# v1.net
KiCad netlist of a schematic drawn in EAGLE
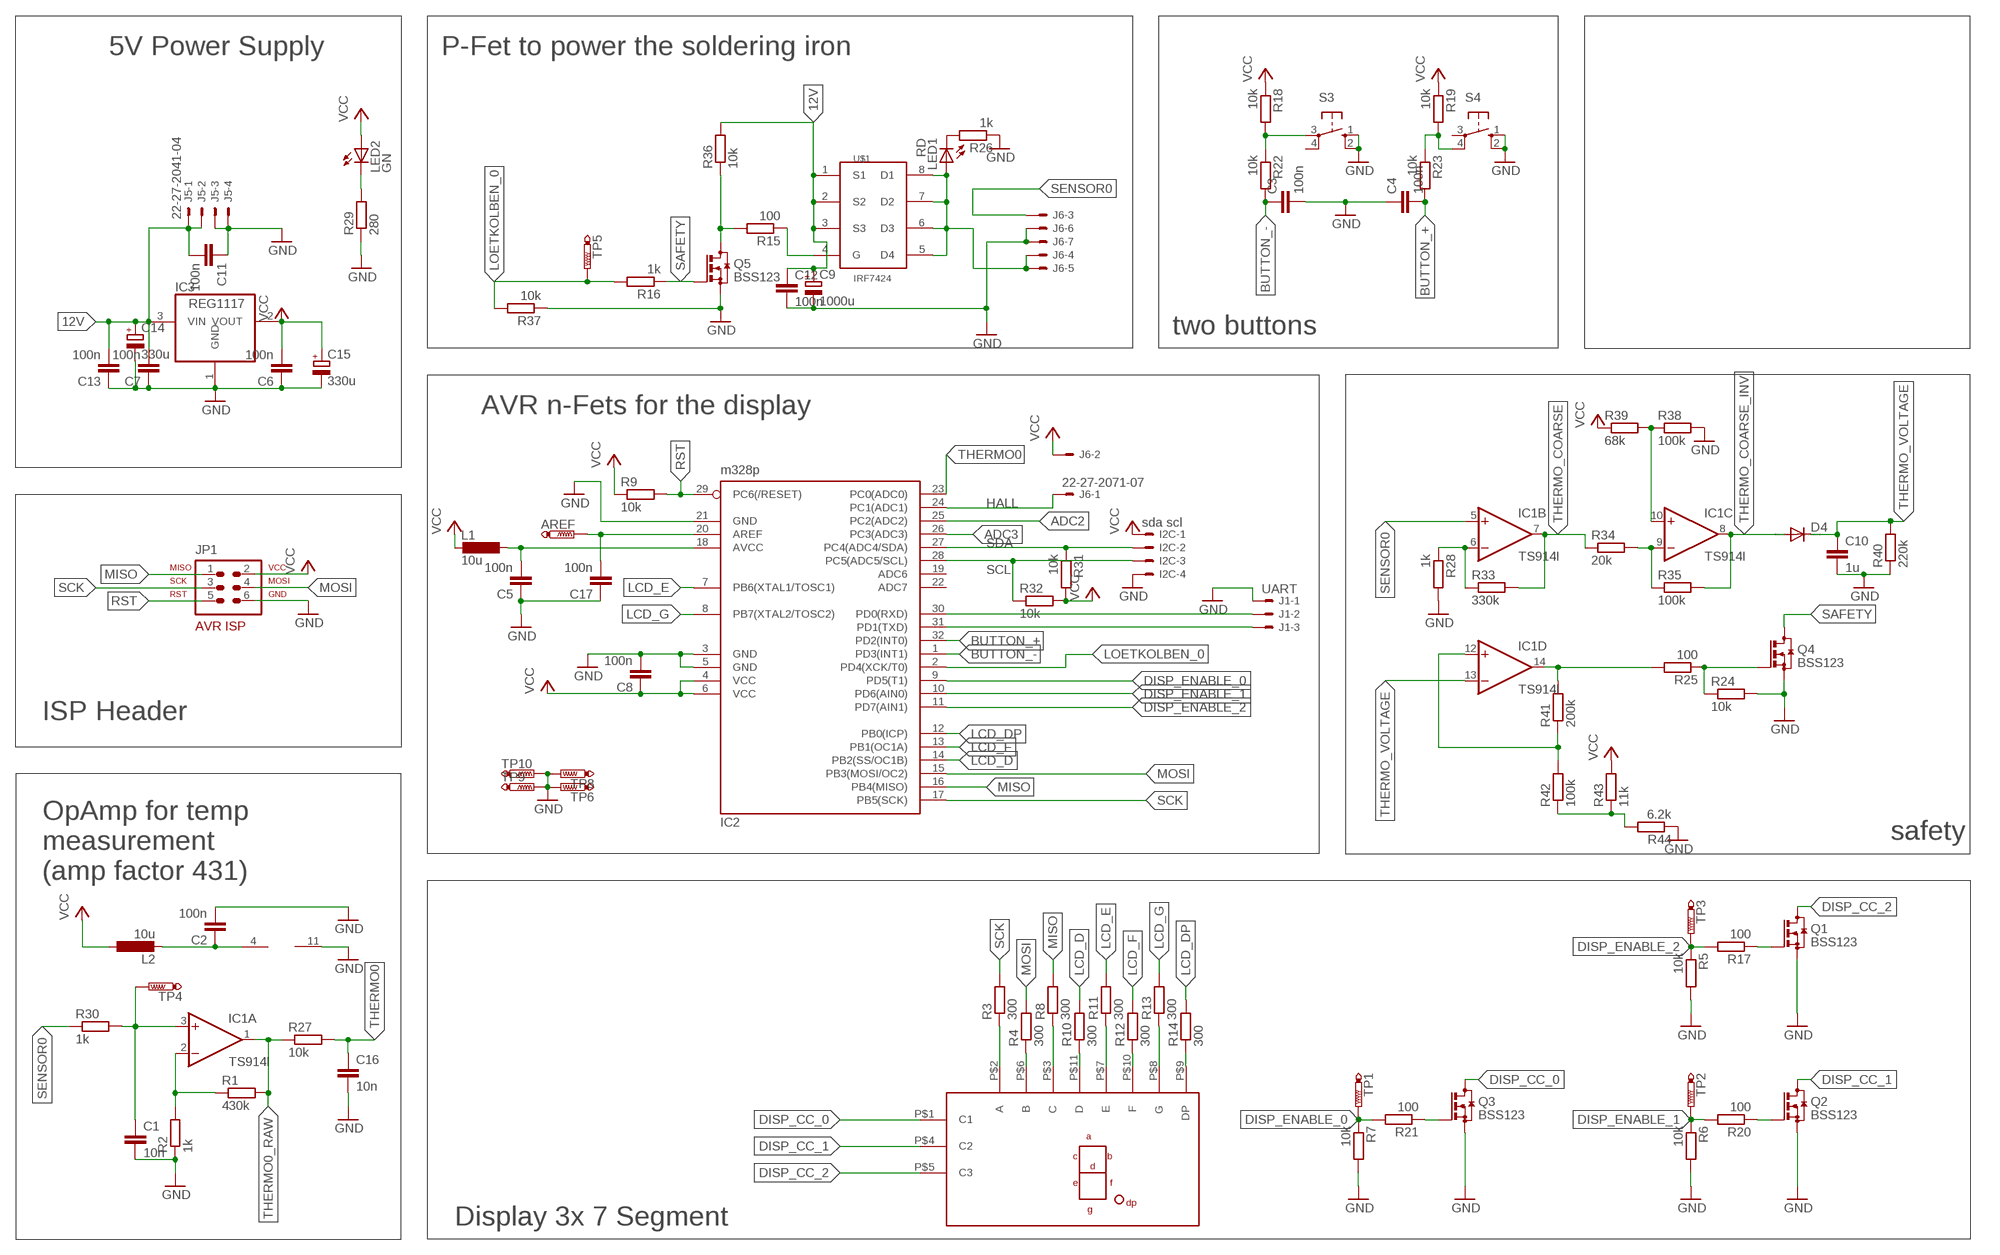
[diagram p0: schematic, sheet 1]

(export (version "E")
  (design (tool "Eeschema 10.0.6"))
  (components
    (comp (ref "AREF")
      (value "PTR1B1,27")
      (footprint "eagle-import:B1,27")
      (libsource (lib "eagle-import") (part "PTR1B1,27"))
    )
    (comp (ref "C1")
      (value "10n")
      (footprint "eagle-import:C0603")
      (libsource (lib "eagle-import") (part "C-EUC0603"))
    )
    (comp (ref "C2")
      (value "100n")
      (footprint "eagle-import:C0603")
      (libsource (lib "eagle-import") (part "C-EUC0603"))
    )
    (comp (ref "C3")
      (value "100n")
      (footprint "eagle-import:C0603")
      (libsource (lib "eagle-import") (part "C-EUC0603"))
    )
    (comp (ref "C4")
      (value "100n")
      (footprint "eagle-import:C0603")
      (libsource (lib "eagle-import") (part "C-EUC0603"))
    )
    (comp (ref "C5")
      (value "100n")
      (footprint "eagle-import:C0603")
      (libsource (lib "eagle-import") (part "C-EUC0603"))
    )
    (comp (ref "C6")
      (value "100n")
      (footprint "eagle-import:C0603")
      (libsource (lib "eagle-import") (part "C-EUC0603"))
    )
    (comp (ref "C7")
      (value "100n")
      (footprint "eagle-import:C0603")
      (libsource (lib "eagle-import") (part "C-EUC0603"))
    )
    (comp (ref "C8")
      (value "100n")
      (footprint "eagle-import:C0603")
      (libsource (lib "eagle-import") (part "C-EUC0603"))
    )
    (comp (ref "C9")
      (value "1000u")
      (footprint "eagle-import:E5-13")
      (libsource (lib "eagle-import") (part "CPOL-EUE5-13"))
    )
    (comp (ref "C10")
      (value "1u")
      (footprint "eagle-import:C0805")
      (libsource (lib "eagle-import") (part "C-EUC0805"))
    )
    (comp (ref "C11")
      (value "100n")
      (footprint "eagle-import:C0603")
      (libsource (lib "eagle-import") (part "C-EUC0603"))
    )
    (comp (ref "C12")
      (value "100n")
      (footprint "eagle-import:C0603")
      (libsource (lib "eagle-import") (part "C-EUC0603"))
    )
    (comp (ref "C13")
      (value "100n")
      (footprint "eagle-import:C0603")
      (libsource (lib "eagle-import") (part "C-EUC0603"))
    )
    (comp (ref "C14")
      (value "330u")
      (footprint "eagle-import:E3,5-8")
      (libsource (lib "eagle-import") (part "CPOL-EUE3.5-8"))
    )
    (comp (ref "C15")
      (value "330u")
      (footprint "eagle-import:E2-5")
      (libsource (lib "eagle-import") (part "CPOL-EUE2-5"))
    )
    (comp (ref "C16")
      (value "10n")
      (footprint "eagle-import:C0603")
      (libsource (lib "eagle-import") (part "C-EUC0603"))
    )
    (comp (ref "C17")
      (value "100n")
      (footprint "eagle-import:C0603")
      (libsource (lib "eagle-import") (part "C-EUC0603"))
    )
    (comp (ref "D4")
      (value "DIODE-DO214AC")
      (footprint "eagle-import:DO214AC")
      (libsource (lib "eagle-import") (part "DIODE-DO214AC"))
    )
    (comp (ref "I2C")
      (value "sda scl")
      (footprint "eagle-import:6410-04")
      (libsource (lib "eagle-import") (part "22-?-0427-2041"))
    )
    (comp (ref "IC1")
      (value "TS914I")
      (footprint "eagle-import:SO14")
      (libsource (lib "eagle-import") (part "LM324D"))
    )
    (comp (ref "IC2")
      (value "m328p")
      (footprint "eagle-import:TQFP32-08")
      (fields (field (name "MPN") "ATMEGA8-16AU"))
      (libsource (lib "eagle-import") (part "MEGA8-AI"))
    )
    (comp (ref "IC3")
      (value "REG1117")
      (footprint "eagle-import:SOT223")
      (libsource (lib "eagle-import") (part "REG1117"))
    )
    (comp (ref "J1")
      (value "UART")
      (footprint "eagle-import:6410-03")
      (libsource (lib "eagle-import") (part "22-?-0327-2031"))
    )
    (comp (ref "J5")
      (value "22-27-2041-04")
      (footprint "eagle-import:6410-04")
      (libsource (lib "eagle-import") (part "22-?-0427-2041"))
    )
    (comp (ref "J6")
      (value "22-27-2071-07")
      (footprint "eagle-import:6410-07")
      (libsource (lib "eagle-import") (part "22-?-0727-2071"))
    )
    (comp (ref "JP1")
      (value "AVR-ISP-6VERT")
      (footprint "eagle-import:AVR-ISP-6")
      (libsource (lib "eagle-import") (part "AVR-ISP-6VERT"))
    )
    (comp (ref "L1")
      (value "10u")
      (footprint "eagle-import:L2825P")
      (libsource (lib "eagle-import") (part "L-EUL2825P"))
    )
    (comp (ref "L2")
      (value "10u")
      (footprint "eagle-import:L2825P")
      (libsource (lib "eagle-import") (part "L-EUL2825P"))
    )
    (comp (ref "LED1")
      (value "RD")
      (footprint "eagle-import:CHIP-LED0805")
      (libsource (lib "eagle-import") (part "LEDCHIP-LED0805"))
    )
    (comp (ref "LED2")
      (value "GN")
      (footprint "eagle-import:CHIP-LED0805")
      (libsource (lib "eagle-import") (part "LEDCHIP-LED0805"))
    )
    (comp (ref "Q1")
      (value "BSS123")
      (footprint "eagle-import:SOT23")
      (libsource (lib "eagle-import") (part "BSS123"))
    )
    (comp (ref "Q2")
      (value "BSS123")
      (footprint "eagle-import:SOT23")
      (libsource (lib "eagle-import") (part "BSS123"))
    )
    (comp (ref "Q3")
      (value "BSS123")
      (footprint "eagle-import:SOT23")
      (libsource (lib "eagle-import") (part "BSS123"))
    )
    (comp (ref "Q4")
      (value "BSS123")
      (footprint "eagle-import:SOT23")
      (libsource (lib "eagle-import") (part "BSS123"))
    )
    (comp (ref "Q5")
      (value "BSS123")
      (footprint "eagle-import:SOT23")
      (libsource (lib "eagle-import") (part "BSS123"))
    )
    (comp (ref "R1")
      (value "430k")
      (footprint "eagle-import:R0603")
      (libsource (lib "eagle-import") (part "R-EU_R0603"))
    )
    (comp (ref "R2")
      (value "1k")
      (footprint "eagle-import:R0603")
      (libsource (lib "eagle-import") (part "R-EU_R0603"))
    )
    (comp (ref "R3")
      (value "300")
      (footprint "eagle-import:R0603")
      (libsource (lib "eagle-import") (part "R-EU_R0603"))
    )
    (comp (ref "R4")
      (value "300")
      (footprint "eagle-import:R0603")
      (libsource (lib "eagle-import") (part "R-EU_R0603"))
    )
    (comp (ref "R5")
      (value "10k")
      (footprint "eagle-import:R0603")
      (libsource (lib "eagle-import") (part "R-EU_R0603"))
    )
    (comp (ref "R6")
      (value "10k")
      (footprint "eagle-import:R0603")
      (libsource (lib "eagle-import") (part "R-EU_R0603"))
    )
    (comp (ref "R7")
      (value "10k")
      (footprint "eagle-import:R0603")
      (libsource (lib "eagle-import") (part "R-EU_R0603"))
    )
    (comp (ref "R8")
      (value "300")
      (footprint "eagle-import:R0603")
      (libsource (lib "eagle-import") (part "R-EU_R0603"))
    )
    (comp (ref "R9")
      (value "10k")
      (footprint "eagle-import:R0603")
      (libsource (lib "eagle-import") (part "R-EU_R0603"))
    )
    (comp (ref "R10")
      (value "300")
      (footprint "eagle-import:R0603")
      (libsource (lib "eagle-import") (part "R-EU_R0603"))
    )
    (comp (ref "R11")
      (value "300")
      (footprint "eagle-import:R0603")
      (libsource (lib "eagle-import") (part "R-EU_R0603"))
    )
    (comp (ref "R12")
      (value "300")
      (footprint "eagle-import:R0603")
      (libsource (lib "eagle-import") (part "R-EU_R0603"))
    )
    (comp (ref "R13")
      (value "300")
      (footprint "eagle-import:R0603")
      (libsource (lib "eagle-import") (part "R-EU_R0603"))
    )
    (comp (ref "R14")
      (value "300")
      (footprint "eagle-import:R0603")
      (libsource (lib "eagle-import") (part "R-EU_R0603"))
    )
    (comp (ref "R15")
      (value "100")
      (footprint "eagle-import:R0603")
      (libsource (lib "eagle-import") (part "R-EU_R0603"))
    )
    (comp (ref "R16")
      (value "1k")
      (footprint "eagle-import:R0603")
      (libsource (lib "eagle-import") (part "R-EU_R0603"))
    )
    (comp (ref "R17")
      (value "100")
      (footprint "eagle-import:R0603")
      (libsource (lib "eagle-import") (part "R-EU_R0603"))
    )
    (comp (ref "R18")
      (value "10k")
      (footprint "eagle-import:R0603")
      (libsource (lib "eagle-import") (part "R-EU_R0603"))
    )
    (comp (ref "R19")
      (value "10k")
      (footprint "eagle-import:R0603")
      (libsource (lib "eagle-import") (part "R-EU_R0603"))
    )
    (comp (ref "R20")
      (value "100")
      (footprint "eagle-import:R0603")
      (libsource (lib "eagle-import") (part "R-EU_R0603"))
    )
    (comp (ref "R21")
      (value "100")
      (footprint "eagle-import:R0603")
      (libsource (lib "eagle-import") (part "R-EU_R0603"))
    )
    (comp (ref "R22")
      (value "10k")
      (footprint "eagle-import:R0603")
      (libsource (lib "eagle-import") (part "R-EU_R0603"))
    )
    (comp (ref "R23")
      (value "10k")
      (footprint "eagle-import:R0603")
      (libsource (lib "eagle-import") (part "R-EU_R0603"))
    )
    (comp (ref "R24")
      (value "10k")
      (footprint "eagle-import:R0603")
      (libsource (lib "eagle-import") (part "R-EU_R0603"))
    )
    (comp (ref "R25")
      (value "100")
      (footprint "eagle-import:R0603")
      (libsource (lib "eagle-import") (part "R-EU_R0603"))
    )
    (comp (ref "R26")
      (value "1k")
      (footprint "eagle-import:R0603")
      (libsource (lib "eagle-import") (part "R-EU_R0603"))
    )
    (comp (ref "R27")
      (value "10k")
      (footprint "eagle-import:R0603")
      (libsource (lib "eagle-import") (part "R-EU_R0603"))
    )
    (comp (ref "R28")
      (value "1k")
      (footprint "eagle-import:R0603")
      (libsource (lib "eagle-import") (part "R-EU_R0603"))
    )
    (comp (ref "R29")
      (value "280")
      (footprint "eagle-import:R0603")
      (libsource (lib "eagle-import") (part "R-EU_R0603"))
    )
    (comp (ref "R30")
      (value "1k")
      (footprint "eagle-import:R0603")
      (libsource (lib "eagle-import") (part "R-EU_R0603"))
    )
    (comp (ref "R31")
      (value "10k")
      (footprint "eagle-import:R0603")
      (libsource (lib "eagle-import") (part "R-EU_R0603"))
    )
    (comp (ref "R32")
      (value "10k")
      (footprint "eagle-import:R0603")
      (libsource (lib "eagle-import") (part "R-EU_R0603"))
    )
    (comp (ref "R33")
      (value "330k")
      (footprint "eagle-import:R0603")
      (libsource (lib "eagle-import") (part "R-EU_R0603"))
    )
    (comp (ref "R34")
      (value "20k")
      (footprint "eagle-import:R0603")
      (libsource (lib "eagle-import") (part "R-EU_R0603"))
    )
    (comp (ref "R35")
      (value "100k")
      (footprint "eagle-import:R0603")
      (libsource (lib "eagle-import") (part "R-EU_R0603"))
    )
    (comp (ref "R36")
      (value "10k")
      (footprint "eagle-import:R0603")
      (libsource (lib "eagle-import") (part "R-EU_R0603"))
    )
    (comp (ref "R37")
      (value "10k")
      (footprint "eagle-import:R0603")
      (libsource (lib "eagle-import") (part "R-EU_R0603"))
    )
    (comp (ref "R38")
      (value "100k")
      (footprint "eagle-import:R0603")
      (libsource (lib "eagle-import") (part "R-EU_R0603"))
    )
    (comp (ref "R39")
      (value "68k")
      (footprint "eagle-import:R0603")
      (libsource (lib "eagle-import") (part "R-EU_R0603"))
    )
    (comp (ref "R40")
      (value "220k")
      (footprint "eagle-import:R0603")
      (libsource (lib "eagle-import") (part "R-EU_R0603"))
    )
    (comp (ref "R41")
      (value "200k")
      (footprint "eagle-import:R0603")
      (libsource (lib "eagle-import") (part "R-EU_R0603"))
    )
    (comp (ref "R42")
      (value "100k")
      (footprint "eagle-import:R0603")
      (libsource (lib "eagle-import") (part "R-EU_R0603"))
    )
    (comp (ref "R43")
      (value "11k")
      (footprint "eagle-import:R0603")
      (libsource (lib "eagle-import") (part "R-EU_R0603"))
    )
    (comp (ref "R44")
      (value "6.2k")
      (footprint "eagle-import:R0603")
      (libsource (lib "eagle-import") (part "R-EU_R0603"))
    )
    (comp (ref "S3")
      (value "10-XX")
      (footprint "eagle-import:B3F-10XX")
      (fields (field (name "MPN") "B3F-1000"))
      (libsource (lib "eagle-import") (part "10-XX"))
    )
    (comp (ref "S4")
      (value "10-XX")
      (footprint "eagle-import:B3F-10XX")
      (fields (field (name "MPN") "B3F-1000"))
      (libsource (lib "eagle-import") (part "10-XX"))
    )
    (comp (ref "TP1")
      (value "PTR1B1,27")
      (footprint "eagle-import:B1,27")
      (libsource (lib "eagle-import") (part "PTR1B1,27"))
    )
    (comp (ref "TP2")
      (value "PTR1B1,27")
      (footprint "eagle-import:B1,27")
      (libsource (lib "eagle-import") (part "PTR1B1,27"))
    )
    (comp (ref "TP3")
      (value "PTR1B1,27")
      (footprint "eagle-import:B1,27")
      (libsource (lib "eagle-import") (part "PTR1B1,27"))
    )
    (comp (ref "TP4")
      (value "PTR1B1,27")
      (footprint "eagle-import:B1,27")
      (libsource (lib "eagle-import") (part "PTR1B1,27"))
    )
    (comp (ref "TP5")
      (value "PTR1B1,27")
      (footprint "eagle-import:B1,27")
      (libsource (lib "eagle-import") (part "PTR1B1,27"))
    )
    (comp (ref "TP6")
      (value "PTR1B1,27")
      (footprint "eagle-import:B1,27")
      (libsource (lib "eagle-import") (part "PTR1B1,27"))
    )
    (comp (ref "TP8")
      (value "PTR1B1,27")
      (footprint "eagle-import:B1,27")
      (libsource (lib "eagle-import") (part "PTR1B1,27"))
    )
    (comp (ref "TP9")
      (value "PTR1B1,27")
      (footprint "eagle-import:B1,27")
      (libsource (lib "eagle-import") (part "PTR1B1,27"))
    )
    (comp (ref "TP10")
      (value "PTR1B1,27")
      (footprint "eagle-import:B1,27")
      (libsource (lib "eagle-import") (part "PTR1B1,27"))
    )
    (comp (ref "U$1")
      (value "IRF7424")
      (footprint "eagle-import:SO-08")
      (libsource (lib "eagle-import") (part "IRF7424"))
    )
    (comp (ref "U$2")
      (value "3X7SEG")
      (footprint "eagle-import:3X7SEG")
      (libsource (lib "eagle-import") (part "3X7SEG"))
    )
  )
  (nets
    (net (code "1") (name "/HALL") (class "Default")
      (node (ref "IC2") (pin "24") (pinfunction "PC1(ADC1)_24") (pintype "bidirectional"))
      (node (ref "J6") (pin "1") (pinfunction "S_1") (pintype "passive"))
    )
    (net (code "2") (name "/SCL") (class "Default")
      (node (ref "I2C") (pin "3") (pinfunction "S_3") (pintype "passive"))
      (node (ref "IC2") (pin "28") (pinfunction "PC5(ADC5/SCL)_28") (pintype "bidirectional"))
      (node (ref "R32") (pin "1") (pinfunction "1_1") (pintype "passive"))
    )
    (net (code "3") (name "/SDA") (class "Default")
      (node (ref "I2C") (pin "2") (pinfunction "S_2") (pintype "passive"))
      (node (ref "IC2") (pin "27") (pinfunction "PC4(ADC4/SDA)_27") (pintype "bidirectional"))
      (node (ref "R31") (pin "1") (pinfunction "1_1") (pintype "passive"))
    )
    (net (code "4") (name "12V") (class "Default")
      (node (ref "C11") (pin "2") (pinfunction "2_2") (pintype "passive"))
      (node (ref "C12") (pin "1") (pinfunction "1_1") (pintype "passive"))
      (node (ref "C13") (pin "2") (pinfunction "2_2") (pintype "passive"))
      (node (ref "C14") (pin "+") (pinfunction "+_+") (pintype "passive"))
      (node (ref "C7") (pin "2") (pinfunction "2_2") (pintype "passive"))
      (node (ref "C9") (pin "+") (pinfunction "+_+") (pintype "passive"))
      (node (ref "IC3") (pin "3") (pinfunction "VIN_3") (pintype "input"))
      (node (ref "J5") (pin "1") (pinfunction "S_1") (pintype "passive"))
      (node (ref "J5") (pin "2") (pinfunction "S_2") (pintype "passive"))
      (node (ref "R36") (pin "2") (pinfunction "2_2") (pintype "passive"))
      (node (ref "U$1") (pin "1") (pinfunction "S1_1") (pintype "bidirectional"))
      (node (ref "U$1") (pin "2") (pinfunction "S2_2") (pintype "bidirectional"))
      (node (ref "U$1") (pin "3") (pinfunction "S3_3") (pintype "bidirectional"))
    )
    (net (code "5") (name "ADC2") (class "Default")
      (node (ref "IC2") (pin "25") (pinfunction "PC2(ADC2)_25") (pintype "bidirectional"))
    )
    (net (code "6") (name "ADC3") (class "Default")
      (node (ref "IC2") (pin "26") (pinfunction "PC3(ADC3)_26") (pintype "bidirectional"))
    )
    (net (code "7") (name "BUTTON_+") (class "Default")
      (node (ref "C4") (pin "2") (pinfunction "2_2") (pintype "passive"))
      (node (ref "IC2") (pin "32") (pinfunction "PD2(INT0)_32") (pintype "bidirectional"))
      (node (ref "R23") (pin "2") (pinfunction "2_2") (pintype "passive"))
    )
    (net (code "8") (name "BUTTON_-") (class "Default")
      (node (ref "C3") (pin "1") (pinfunction "1_1") (pintype "passive"))
      (node (ref "IC2") (pin "1") (pinfunction "PD3(INT1)_1") (pintype "bidirectional"))
      (node (ref "R22") (pin "2") (pinfunction "2_2") (pintype "passive"))
    )
    (net (code "9") (name "DISP_CC_0") (class "Default")
      (node (ref "Q3") (pin "3") (pinfunction "D_3") (pintype "passive"))
      (node (ref "U$2") (pin "P$1") (pinfunction "C1_P$1") (pintype "bidirectional"))
    )
    (net (code "10") (name "DISP_CC_1") (class "Default")
      (node (ref "Q2") (pin "3") (pinfunction "D_3") (pintype "passive"))
      (node (ref "U$2") (pin "P$4") (pinfunction "C2_P$4") (pintype "bidirectional"))
    )
    (net (code "11") (name "DISP_CC_2") (class "Default")
      (node (ref "Q1") (pin "3") (pinfunction "D_3") (pintype "passive"))
      (node (ref "U$2") (pin "P$5") (pinfunction "C3_P$5") (pintype "bidirectional"))
    )
    (net (code "12") (name "DISP_ENABLE_0") (class "Default")
      (node (ref "IC2") (pin "9") (pinfunction "PD5(T1)_9") (pintype "bidirectional"))
      (node (ref "R21") (pin "2") (pinfunction "2_2") (pintype "passive"))
      (node (ref "R7") (pin "1") (pinfunction "1_1") (pintype "passive"))
      (node (ref "TP1") (pin "TP") (pinfunction "TP_TP") (pintype "input"))
    )
    (net (code "13") (name "DISP_ENABLE_1") (class "Default")
      (node (ref "IC2") (pin "10") (pinfunction "PD6(AIN0)_10") (pintype "bidirectional"))
      (node (ref "R20") (pin "2") (pinfunction "2_2") (pintype "passive"))
      (node (ref "R6") (pin "1") (pinfunction "1_1") (pintype "passive"))
      (node (ref "TP2") (pin "TP") (pinfunction "TP_TP") (pintype "input"))
    )
    (net (code "14") (name "DISP_ENABLE_2") (class "Default")
      (node (ref "IC2") (pin "11") (pinfunction "PD7(AIN1)_11") (pintype "bidirectional"))
      (node (ref "R17") (pin "2") (pinfunction "2_2") (pintype "passive"))
      (node (ref "R5") (pin "1") (pinfunction "1_1") (pintype "passive"))
      (node (ref "TP3") (pin "TP") (pinfunction "TP_TP") (pintype "input"))
    )
    (net (code "15") (name "GND") (class "Default")
      (node (ref "C1") (pin "2") (pinfunction "2_2") (pintype "passive"))
      (node (ref "C10") (pin "2") (pinfunction "2_2") (pintype "passive"))
      (node (ref "C11") (pin "1") (pinfunction "1_1") (pintype "passive"))
      (node (ref "C12") (pin "2") (pinfunction "2_2") (pintype "passive"))
      (node (ref "C13") (pin "1") (pinfunction "1_1") (pintype "passive"))
      (node (ref "C14") (pin "-") (pinfunction "-_-") (pintype "passive"))
      (node (ref "C15") (pin "-") (pinfunction "-_-") (pintype "passive"))
      (node (ref "C16") (pin "2") (pinfunction "2_2") (pintype "passive"))
      (node (ref "C17") (pin "1") (pinfunction "1_1") (pintype "passive"))
      (node (ref "C2") (pin "2") (pinfunction "2_2") (pintype "passive"))
      (node (ref "C3") (pin "2") (pinfunction "2_2") (pintype "passive"))
      (node (ref "C4") (pin "1") (pinfunction "1_1") (pintype "passive"))
      (node (ref "C5") (pin "1") (pinfunction "1_1") (pintype "passive"))
      (node (ref "C6") (pin "1") (pinfunction "1_1") (pintype "passive"))
      (node (ref "C7") (pin "1") (pinfunction "1_1") (pintype "passive"))
      (node (ref "C8") (pin "2") (pinfunction "2_2") (pintype "passive"))
      (node (ref "C9") (pin "-") (pinfunction "-_-") (pintype "passive"))
      (node (ref "I2C") (pin "4") (pinfunction "S_4") (pintype "passive"))
      (node (ref "IC1") (pin "11") (pinfunction "V-_11") (pintype "power_in"))
      (node (ref "IC2") (pin "21") (pinfunction "GND_21") (pintype "power_in"))
      (node (ref "IC2") (pin "3") (pinfunction "GND_3") (pintype "power_in"))
      (node (ref "IC2") (pin "5") (pinfunction "GND_5") (pintype "power_in"))
      (node (ref "IC3") (pin "1") (pinfunction "GND_1") (pintype "power_in"))
      (node (ref "J1") (pin "1") (pinfunction "S_1") (pintype "passive"))
      (node (ref "J5") (pin "3") (pinfunction "S_3") (pintype "passive"))
      (node (ref "J5") (pin "4") (pinfunction "S_4") (pintype "passive"))
      (node (ref "J6") (pin "6") (pinfunction "S_6") (pintype "passive"))
      (node (ref "J6") (pin "7") (pinfunction "S_7") (pintype "passive"))
      (node (ref "JP1") (pin "6") (pinfunction "6_6") (pintype "passive"))
      (node (ref "Q1") (pin "2") (pinfunction "S_2") (pintype "passive"))
      (node (ref "Q2") (pin "2") (pinfunction "S_2") (pintype "passive"))
      (node (ref "Q3") (pin "2") (pinfunction "S_2") (pintype "passive"))
      (node (ref "Q4") (pin "2") (pinfunction "S_2") (pintype "passive"))
      (node (ref "Q5") (pin "2") (pinfunction "S_2") (pintype "passive"))
      (node (ref "R2") (pin "1") (pinfunction "1_1") (pintype "passive"))
      (node (ref "R24") (pin "2") (pinfunction "2_2") (pintype "passive"))
      (node (ref "R26") (pin "1") (pinfunction "1_1") (pintype "passive"))
      (node (ref "R28") (pin "2") (pinfunction "2_2") (pintype "passive"))
      (node (ref "R29") (pin "1") (pinfunction "1_1") (pintype "passive"))
      (node (ref "R37") (pin "1") (pinfunction "1_1") (pintype "passive"))
      (node (ref "R38") (pin "2") (pinfunction "2_2") (pintype "passive"))
      (node (ref "R40") (pin "1") (pinfunction "1_1") (pintype "passive"))
      (node (ref "R44") (pin "1") (pinfunction "1_1") (pintype "passive"))
      (node (ref "R5") (pin "2") (pinfunction "2_2") (pintype "passive"))
      (node (ref "R6") (pin "2") (pinfunction "2_2") (pintype "passive"))
      (node (ref "R7") (pin "2") (pinfunction "2_2") (pintype "passive"))
      (node (ref "S3") (pin "1") (pinfunction "S_1") (pintype "passive"))
      (node (ref "S3") (pin "2") (pinfunction "S1_2") (pintype "passive"))
      (node (ref "S4") (pin "1") (pinfunction "S_1") (pintype "passive"))
      (node (ref "S4") (pin "2") (pinfunction "S1_2") (pintype "passive"))
      (node (ref "TP10") (pin "TP") (pinfunction "TP_TP") (pintype "input"))
      (node (ref "TP6") (pin "TP") (pinfunction "TP_TP") (pintype "input"))
      (node (ref "TP8") (pin "TP") (pinfunction "TP_TP") (pintype "input"))
      (node (ref "TP9") (pin "TP") (pinfunction "TP_TP") (pintype "input"))
    )
    (net (code "16") (name "LCD_D") (class "Default")
      (node (ref "IC2") (pin "14") (pinfunction "PB2(SS/OC1B)_14") (pintype "bidirectional"))
      (node (ref "R10") (pin "2") (pinfunction "2_2") (pintype "passive"))
    )
    (net (code "17") (name "LCD_DP") (class "Default")
      (node (ref "IC2") (pin "12") (pinfunction "PB0(ICP)_12") (pintype "bidirectional"))
      (node (ref "R14") (pin "2") (pinfunction "2_2") (pintype "passive"))
    )
    (net (code "18") (name "LCD_E") (class "Default")
      (node (ref "IC2") (pin "7") (pinfunction "PB6(XTAL1/TOSC1)_7") (pintype "bidirectional"))
      (node (ref "R11") (pin "2") (pinfunction "2_2") (pintype "passive"))
    )
    (net (code "19") (name "LCD_F") (class "Default")
      (node (ref "IC2") (pin "13") (pinfunction "PB1(OC1A)_13") (pintype "bidirectional"))
      (node (ref "R12") (pin "2") (pinfunction "2_2") (pintype "passive"))
    )
    (net (code "20") (name "LCD_G") (class "Default")
      (node (ref "IC2") (pin "8") (pinfunction "PB7(XTAL2/TOSC2)_8") (pintype "bidirectional"))
      (node (ref "R13") (pin "2") (pinfunction "2_2") (pintype "passive"))
    )
    (net (code "21") (name "LOETKOLBEN_0") (class "Default")
      (node (ref "IC2") (pin "2") (pinfunction "PD4(XCK/T0)_2") (pintype "bidirectional"))
      (node (ref "R16") (pin "2") (pinfunction "2_2") (pintype "passive"))
      (node (ref "R37") (pin "2") (pinfunction "2_2") (pintype "passive"))
      (node (ref "TP5") (pin "TP") (pinfunction "TP_TP") (pintype "input"))
    )
    (net (code "22") (name "MISO") (class "Default")
      (node (ref "IC2") (pin "16") (pinfunction "PB4(MISO)_16") (pintype "bidirectional"))
      (node (ref "JP1") (pin "1") (pinfunction "1_1") (pintype "passive"))
      (node (ref "R8") (pin "2") (pinfunction "2_2") (pintype "passive"))
    )
    (net (code "23") (name "MOSI") (class "Default")
      (node (ref "IC2") (pin "15") (pinfunction "PB3(MOSI/OC2)_15") (pintype "bidirectional"))
      (node (ref "JP1") (pin "4") (pinfunction "4_4") (pintype "passive"))
      (node (ref "R4") (pin "2") (pinfunction "2_2") (pintype "passive"))
    )
    (net (code "24") (name "Net-(IC1A-+IN)") (class "Default")
      (node (ref "C1") (pin "1") (pinfunction "1_1") (pintype "passive"))
      (node (ref "IC1") (pin "3") (pinfunction "+IN_3") (pintype "input"))
      (node (ref "R30") (pin "2") (pinfunction "2_2") (pintype "passive"))
      (node (ref "TP4") (pin "TP") (pinfunction "TP_TP") (pintype "input"))
    )
    (net (code "25") (name "Net-(IC1A--IN)") (class "Default")
      (node (ref "IC1") (pin "2") (pinfunction "-IN_2") (pintype "input"))
      (node (ref "R1") (pin "1") (pinfunction "1_1") (pintype "passive"))
      (node (ref "R2") (pin "2") (pinfunction "2_2") (pintype "passive"))
    )
    (net (code "26") (name "Net-(IC1B--IN)") (class "Default")
      (node (ref "IC1") (pin "6") (pinfunction "-IN_6") (pintype "input"))
      (node (ref "R28") (pin "1") (pinfunction "1_1") (pintype "passive"))
      (node (ref "R33") (pin "1") (pinfunction "1_1") (pintype "passive"))
    )
    (net (code "27") (name "Net-(IC1C-+IN)") (class "Default")
      (node (ref "IC1") (pin "10") (pinfunction "+IN_10") (pintype "input"))
      (node (ref "R38") (pin "1") (pinfunction "1_1") (pintype "passive"))
      (node (ref "R39") (pin "2") (pinfunction "2_2") (pintype "passive"))
    )
    (net (code "28") (name "Net-(IC1C--IN)") (class "Default")
      (node (ref "IC1") (pin "9") (pinfunction "-IN_9") (pintype "input"))
      (node (ref "R34") (pin "2") (pinfunction "2_2") (pintype "passive"))
      (node (ref "R35") (pin "1") (pinfunction "1_1") (pintype "passive"))
    )
    (net (code "29") (name "Net-(IC1D-+IN)") (class "Default")
      (node (ref "IC1") (pin "12") (pinfunction "+IN_12") (pintype "input"))
      (node (ref "R41") (pin "1") (pinfunction "1_1") (pintype "passive"))
      (node (ref "R42") (pin "2") (pinfunction "2_2") (pintype "passive"))
    )
    (net (code "30") (name "Net-(IC1D-OUT)") (class "Default")
      (node (ref "IC1") (pin "14") (pinfunction "OUT_14") (pintype "output"))
      (node (ref "R25") (pin "2") (pinfunction "2_2") (pintype "passive"))
      (node (ref "R41") (pin "2") (pinfunction "2_2") (pintype "passive"))
    )
    (net (code "31") (name "Net-(IC1E-V+)") (class "Default")
      (node (ref "C2") (pin "1") (pinfunction "1_1") (pintype "passive"))
      (node (ref "IC1") (pin "4") (pinfunction "V+_4") (pintype "power_in"))
      (node (ref "L2") (pin "2") (pinfunction "2_2") (pintype "passive"))
    )
    (net (code "32") (name "Net-(IC2-AREF)") (class "Default")
      (node (ref "AREF") (pin "TP") (pinfunction "TP_TP") (pintype "input"))
      (node (ref "C17") (pin "2") (pinfunction "2_2") (pintype "passive"))
      (node (ref "IC2") (pin "20") (pinfunction "AREF_20") (pintype "passive"))
    )
    (net (code "33") (name "Net-(IC2-AVCC)") (class "Default")
      (node (ref "C5") (pin "2") (pinfunction "2_2") (pintype "passive"))
      (node (ref "IC2") (pin "18") (pinfunction "AVCC_18") (pintype "power_in"))
      (node (ref "L1") (pin "1") (pinfunction "1_1") (pintype "passive"))
    )
    (net (code "34") (name "Net-(IC2-PD0(RXD))") (class "Default")
      (node (ref "IC2") (pin "30") (pinfunction "PD0(RXD)_30") (pintype "bidirectional"))
      (node (ref "J1") (pin "2") (pinfunction "S_2") (pintype "passive"))
    )
    (net (code "35") (name "Net-(IC2-PD1(TXD))") (class "Default")
      (node (ref "IC2") (pin "31") (pinfunction "PD1(TXD)_31") (pintype "bidirectional"))
      (node (ref "J1") (pin "3") (pinfunction "S_3") (pintype "passive"))
    )
    (net (code "36") (name "Net-(J6D-S)") (class "Default")
      (node (ref "J6") (pin "4") (pinfunction "S_4") (pintype "passive"))
      (node (ref "J6") (pin "5") (pinfunction "S_5") (pintype "passive"))
      (node (ref "LED1") (pin "A") (pinfunction "A_A") (pintype "passive"))
      (node (ref "U$1") (pin "5") (pinfunction "D4_5") (pintype "bidirectional"))
      (node (ref "U$1") (pin "6") (pinfunction "D3_6") (pintype "bidirectional"))
      (node (ref "U$1") (pin "7") (pinfunction "D2_7") (pintype "bidirectional"))
      (node (ref "U$1") (pin "8") (pinfunction "D1_8") (pintype "bidirectional"))
    )
    (net (code "37") (name "Net-(LED1-PadC)") (class "Default")
      (node (ref "LED1") (pin "C") (pinfunction "C_C") (pintype "passive"))
      (node (ref "R26") (pin "2") (pinfunction "2_2") (pintype "passive"))
    )
    (net (code "38") (name "Net-(LED2-PadC)") (class "Default")
      (node (ref "LED2") (pin "C") (pinfunction "C_C") (pintype "passive"))
      (node (ref "R29") (pin "2") (pinfunction "2_2") (pintype "passive"))
    )
    (net (code "39") (name "Net-(Q1-G)") (class "Default")
      (node (ref "Q1") (pin "1") (pinfunction "G_1") (pintype "passive"))
      (node (ref "R17") (pin "1") (pinfunction "1_1") (pintype "passive"))
    )
    (net (code "40") (name "Net-(Q2-G)") (class "Default")
      (node (ref "Q2") (pin "1") (pinfunction "G_1") (pintype "passive"))
      (node (ref "R20") (pin "1") (pinfunction "1_1") (pintype "passive"))
    )
    (net (code "41") (name "Net-(Q3-G)") (class "Default")
      (node (ref "Q3") (pin "1") (pinfunction "G_1") (pintype "passive"))
      (node (ref "R21") (pin "1") (pinfunction "1_1") (pintype "passive"))
    )
    (net (code "42") (name "Net-(Q4-G)") (class "Default")
      (node (ref "Q4") (pin "1") (pinfunction "G_1") (pintype "passive"))
      (node (ref "R24") (pin "1") (pinfunction "1_1") (pintype "passive"))
      (node (ref "R25") (pin "1") (pinfunction "1_1") (pintype "passive"))
    )
    (net (code "43") (name "Net-(Q5-D)") (class "Default")
      (node (ref "Q5") (pin "3") (pinfunction "D_3") (pintype "passive"))
      (node (ref "R15") (pin "2") (pinfunction "2_2") (pintype "passive"))
      (node (ref "R36") (pin "1") (pinfunction "1_1") (pintype "passive"))
    )
    (net (code "44") (name "Net-(R42-Pad1)") (class "Default")
      (node (ref "R42") (pin "1") (pinfunction "1_1") (pintype "passive"))
      (node (ref "R43") (pin "1") (pinfunction "1_1") (pintype "passive"))
      (node (ref "R44") (pin "2") (pinfunction "2_2") (pintype "passive"))
    )
    (net (code "45") (name "Net-(S3-P)") (class "Default")
      (node (ref "R18") (pin "2") (pinfunction "2_2") (pintype "passive"))
      (node (ref "R22") (pin "1") (pinfunction "1_1") (pintype "passive"))
      (node (ref "S3") (pin "3") (pinfunction "P_3") (pintype "passive"))
    )
    (net (code "46") (name "Net-(S4-P1)") (class "Default")
      (node (ref "R19") (pin "2") (pinfunction "2_2") (pintype "passive"))
      (node (ref "R23") (pin "1") (pinfunction "1_1") (pintype "passive"))
      (node (ref "S4") (pin "4") (pinfunction "P1_4") (pintype "passive"))
    )
    (net (code "47") (name "Net-(U$1-G)") (class "Default")
      (node (ref "R15") (pin "1") (pinfunction "1_1") (pintype "passive"))
      (node (ref "U$1") (pin "4") (pinfunction "G_4") (pintype "bidirectional"))
    )
    (net (code "48") (name "Net-(U$2-A)") (class "Default")
      (node (ref "R3") (pin "1") (pinfunction "1_1") (pintype "passive"))
      (node (ref "U$2") (pin "P$2") (pinfunction "A_P$2") (pintype "bidirectional"))
    )
    (net (code "49") (name "Net-(U$2-B)") (class "Default")
      (node (ref "R4") (pin "1") (pinfunction "1_1") (pintype "passive"))
      (node (ref "U$2") (pin "P$6") (pinfunction "B_P$6") (pintype "bidirectional"))
    )
    (net (code "50") (name "Net-(U$2-C)") (class "Default")
      (node (ref "R8") (pin "1") (pinfunction "1_1") (pintype "passive"))
      (node (ref "U$2") (pin "P$3") (pinfunction "C_P$3") (pintype "bidirectional"))
    )
    (net (code "51") (name "Net-(U$2-D)") (class "Default")
      (node (ref "R10") (pin "1") (pinfunction "1_1") (pintype "passive"))
      (node (ref "U$2") (pin "P$11") (pinfunction "D_P$11") (pintype "bidirectional"))
    )
    (net (code "52") (name "Net-(U$2-DP)") (class "Default")
      (node (ref "R14") (pin "1") (pinfunction "1_1") (pintype "passive"))
      (node (ref "U$2") (pin "P$9") (pinfunction "DP_P$9") (pintype "bidirectional"))
    )
    (net (code "53") (name "Net-(U$2-E)") (class "Default")
      (node (ref "R11") (pin "1") (pinfunction "1_1") (pintype "passive"))
      (node (ref "U$2") (pin "P$7") (pinfunction "E_P$7") (pintype "bidirectional"))
    )
    (net (code "54") (name "Net-(U$2-F)") (class "Default")
      (node (ref "R12") (pin "1") (pinfunction "1_1") (pintype "passive"))
      (node (ref "U$2") (pin "P$10") (pinfunction "F_P$10") (pintype "bidirectional"))
    )
    (net (code "55") (name "Net-(U$2-G)") (class "Default")
      (node (ref "R13") (pin "1") (pinfunction "1_1") (pintype "passive"))
      (node (ref "U$2") (pin "P$8") (pinfunction "G_P$8") (pintype "bidirectional"))
    )
    (net (code "56") (name "RST") (class "Default")
      (node (ref "IC2") (pin "29") (pinfunction "PC6(/RESET)_29") (pintype "bidirectional"))
      (node (ref "JP1") (pin "5") (pinfunction "5_5") (pintype "passive"))
      (node (ref "R9") (pin "2") (pinfunction "2_2") (pintype "passive"))
    )
    (net (code "57") (name "SAFETY") (class "Default")
      (node (ref "Q4") (pin "3") (pinfunction "D_3") (pintype "passive"))
      (node (ref "Q5") (pin "1") (pinfunction "G_1") (pintype "passive"))
      (node (ref "R16") (pin "1") (pinfunction "1_1") (pintype "passive"))
    )
    (net (code "58") (name "SCK") (class "Default")
      (node (ref "IC2") (pin "17") (pinfunction "PB5(SCK)_17") (pintype "bidirectional"))
      (node (ref "JP1") (pin "3") (pinfunction "3_3") (pintype "passive"))
      (node (ref "R3") (pin "2") (pinfunction "2_2") (pintype "passive"))
    )
    (net (code "59") (name "SENSOR0") (class "Default")
      (node (ref "IC1") (pin "5") (pinfunction "+IN_5") (pintype "input"))
      (node (ref "J6") (pin "3") (pinfunction "S_3") (pintype "passive"))
      (node (ref "R30") (pin "1") (pinfunction "1_1") (pintype "passive"))
    )
    (net (code "60") (name "THERMO0") (class "Default")
      (node (ref "C16") (pin "1") (pinfunction "1_1") (pintype "passive"))
      (node (ref "IC2") (pin "23") (pinfunction "PC0(ADC0)_23") (pintype "bidirectional"))
      (node (ref "R27") (pin "2") (pinfunction "2_2") (pintype "passive"))
    )
    (net (code "61") (name "THERMO0_RAW") (class "Default")
      (node (ref "IC1") (pin "1") (pinfunction "OUT_1") (pintype "output"))
      (node (ref "R1") (pin "2") (pinfunction "2_2") (pintype "passive"))
      (node (ref "R27") (pin "1") (pinfunction "1_1") (pintype "passive"))
    )
    (net (code "62") (name "THERMO_COARSE") (class "Default")
      (node (ref "IC1") (pin "7") (pinfunction "OUT_7") (pintype "output"))
      (node (ref "R33") (pin "2") (pinfunction "2_2") (pintype "passive"))
      (node (ref "R34") (pin "1") (pinfunction "1_1") (pintype "passive"))
    )
    (net (code "63") (name "THERMO_COARSE_INV") (class "Default")
      (node (ref "D4") (pin "A") (pinfunction "A_A") (pintype "passive"))
      (node (ref "IC1") (pin "8") (pinfunction "OUT_8") (pintype "output"))
      (node (ref "R35") (pin "2") (pinfunction "2_2") (pintype "passive"))
    )
    (net (code "64") (name "THERMO_VOLTAGE") (class "Default")
      (node (ref "C10") (pin "1") (pinfunction "1_1") (pintype "passive"))
      (node (ref "D4") (pin "C") (pinfunction "C_C") (pintype "passive"))
      (node (ref "IC1") (pin "13") (pinfunction "-IN_13") (pintype "input"))
      (node (ref "R40") (pin "2") (pinfunction "2_2") (pintype "passive"))
    )
    (net (code "65") (name "VCC") (class "Default")
      (node (ref "C15") (pin "+") (pinfunction "+_+") (pintype "passive"))
      (node (ref "C6") (pin "2") (pinfunction "2_2") (pintype "passive"))
      (node (ref "C8") (pin "1") (pinfunction "1_1") (pintype "passive"))
      (node (ref "I2C") (pin "1") (pinfunction "S_1") (pintype "passive"))
      (node (ref "IC2") (pin "4") (pinfunction "VCC_4") (pintype "power_in"))
      (node (ref "IC2") (pin "6") (pinfunction "VCC_6") (pintype "power_in"))
      (node (ref "IC3") (pin "2") (pinfunction "VOUT_2") (pintype "output"))
      (node (ref "J6") (pin "2") (pinfunction "S_2") (pintype "passive"))
      (node (ref "JP1") (pin "2") (pinfunction "2_2") (pintype "passive"))
      (node (ref "L1") (pin "2") (pinfunction "2_2") (pintype "passive"))
      (node (ref "L2") (pin "1") (pinfunction "1_1") (pintype "passive"))
      (node (ref "LED2") (pin "A") (pinfunction "A_A") (pintype "passive"))
      (node (ref "R18") (pin "1") (pinfunction "1_1") (pintype "passive"))
      (node (ref "R19") (pin "1") (pinfunction "1_1") (pintype "passive"))
      (node (ref "R31") (pin "2") (pinfunction "2_2") (pintype "passive"))
      (node (ref "R32") (pin "2") (pinfunction "2_2") (pintype "passive"))
      (node (ref "R39") (pin "1") (pinfunction "1_1") (pintype "passive"))
      (node (ref "R43") (pin "2") (pinfunction "2_2") (pintype "passive"))
      (node (ref "R9") (pin "1") (pinfunction "1_1") (pintype "passive"))
    )
    (net (code "66") (name "unconnected-(IC2-ADC6-Pad19)") (class "Default")
      (node (ref "IC2") (pin "19") (pinfunction "ADC6_19") (pintype "bidirectional"))
    )
    (net (code "67") (name "unconnected-(IC2-ADC7-Pad22)") (class "Default")
      (node (ref "IC2") (pin "22") (pinfunction "ADC7_22") (pintype "bidirectional"))
    )
    (net (code "68") (name "unconnected-(S3-P1-Pad4)") (class "Default")
      (node (ref "S3") (pin "4") (pinfunction "P1_4") (pintype "passive"))
    )
    (net (code "69") (name "unconnected-(S4-P-Pad3)") (class "Default")
      (node (ref "S4") (pin "3") (pinfunction "P_3") (pintype "passive"))
    )
  )
)
